# esp8285.net
KiCad netlist of a schematic drawn in EAGLE
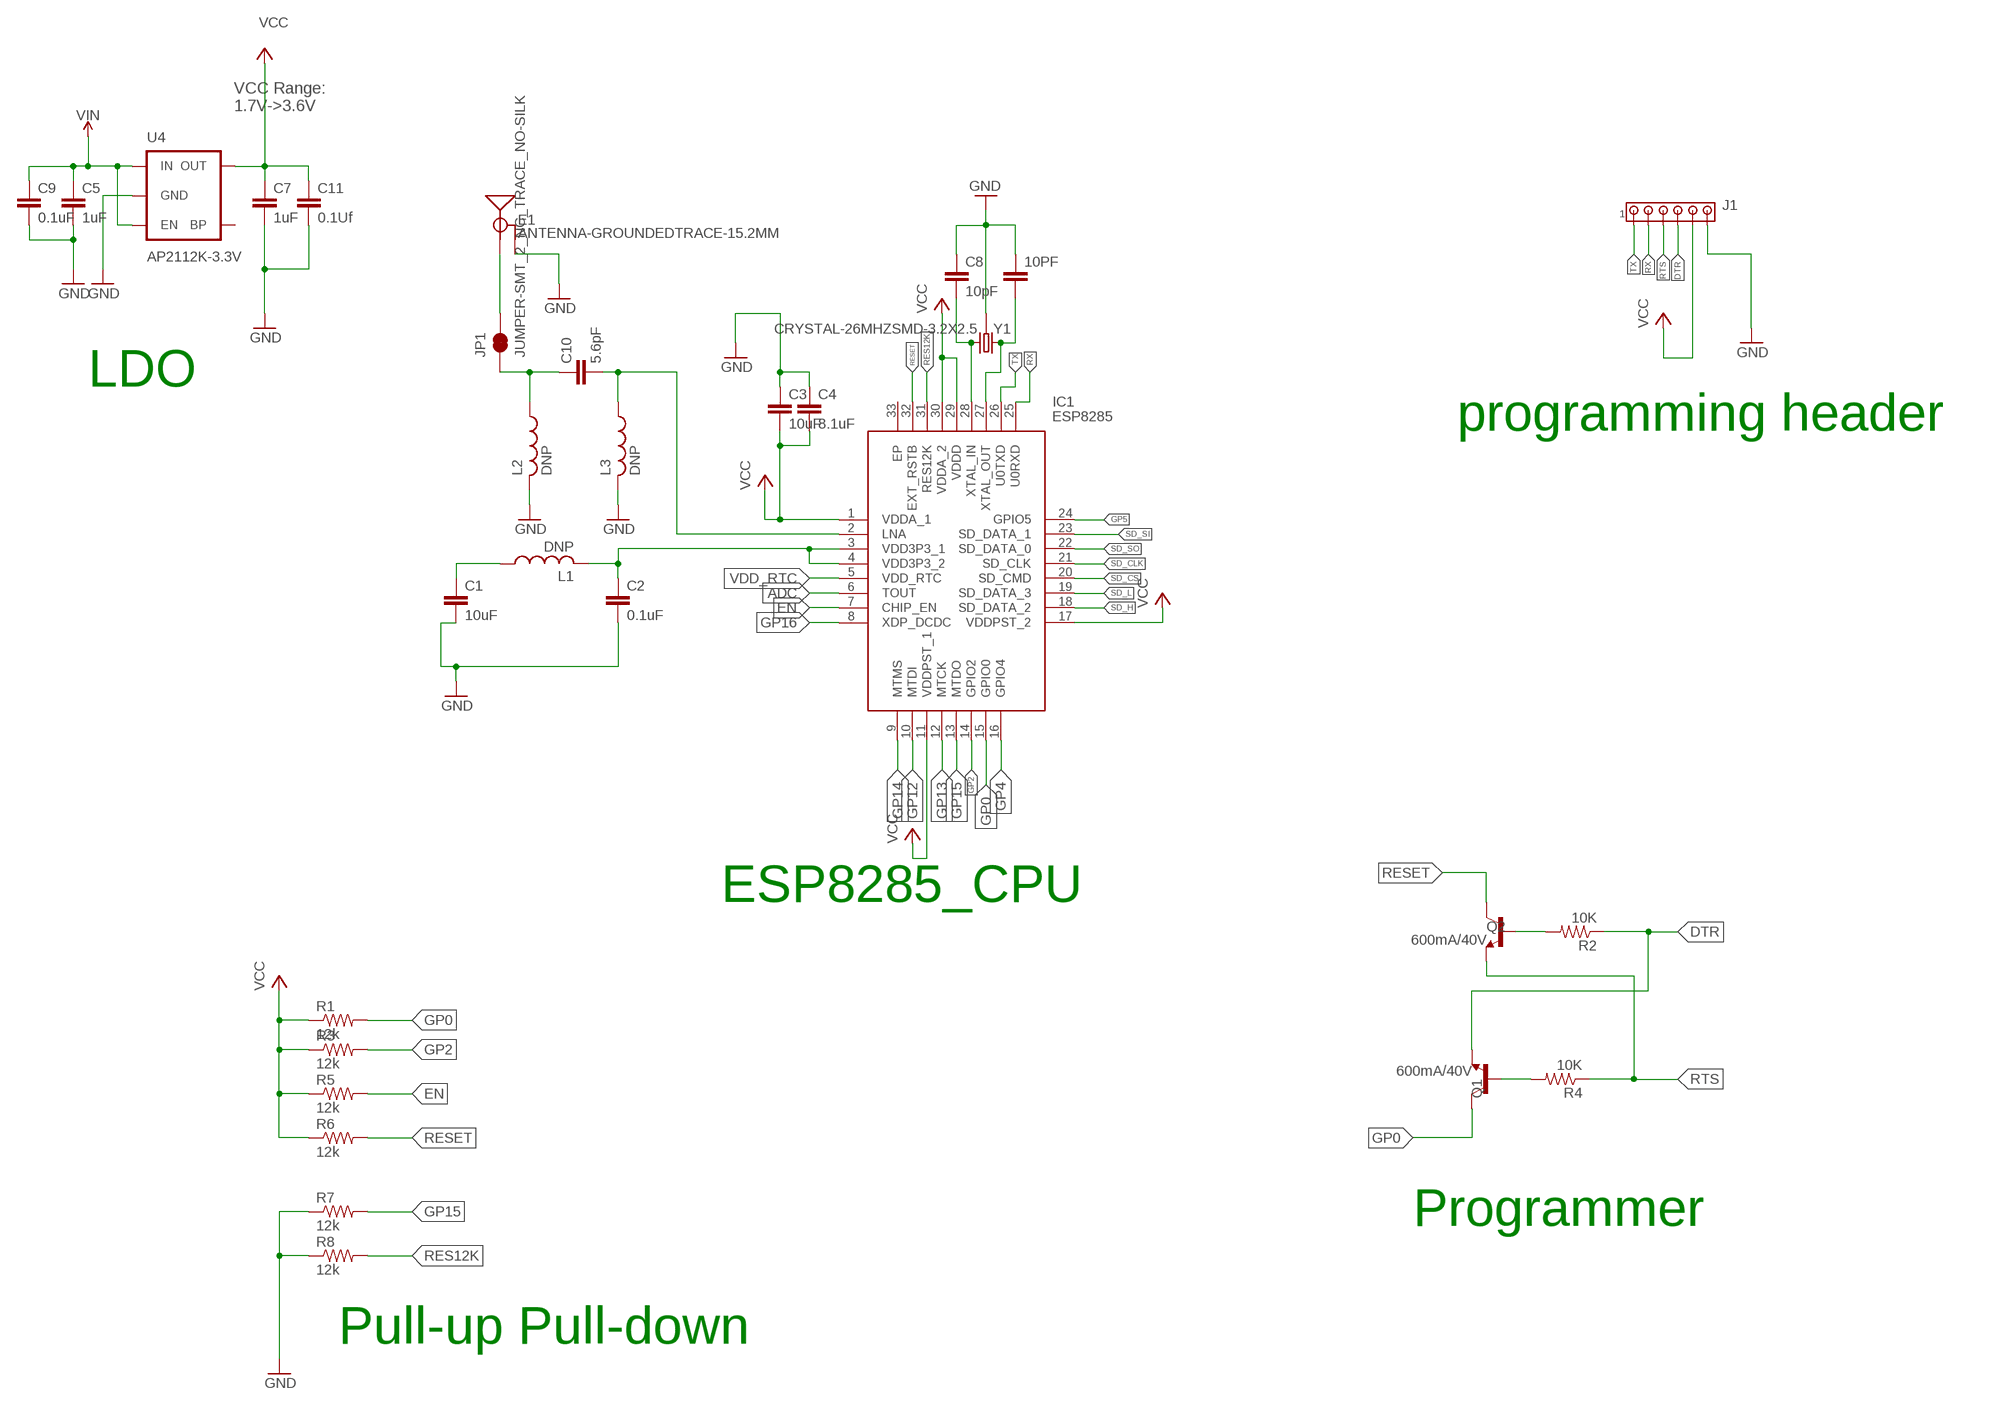
[diagram p0: schematic, sheet 1]

(export (version "E")
  (design (tool "Eeschema 10.0.6"))
  (components
    (comp (ref "10PF")
      (value "C-EUC0603")
      (footprint "eagle-import:C0603")
      (libsource (lib "eagle-import") (part "C-EUC0603"))
    )
    (comp (ref "C1")
      (value "10uF")
      (footprint "eagle-import:C0603")
      (libsource (lib "eagle-import") (part "C-EUC0603"))
    )
    (comp (ref "C2")
      (value "0.1uF")
      (footprint "eagle-import:C0603")
      (libsource (lib "eagle-import") (part "C-EUC0603"))
    )
    (comp (ref "C3")
      (value "10uF")
      (footprint "eagle-import:C0603")
      (libsource (lib "eagle-import") (part "C-EUC0603"))
    )
    (comp (ref "C4")
      (value "8.1uF")
      (footprint "eagle-import:C0603")
      (libsource (lib "eagle-import") (part "C-EUC0603"))
    )
    (comp (ref "C5")
      (value "1uF")
      (footprint "eagle-import:C0603")
      (libsource (lib "eagle-import") (part "C-EUC0603"))
    )
    (comp (ref "C7")
      (value "1uF")
      (footprint "eagle-import:C0603")
      (libsource (lib "eagle-import") (part "C-EUC0603"))
    )
    (comp (ref "C8")
      (value "10pF")
      (footprint "eagle-import:C0603")
      (libsource (lib "eagle-import") (part "C-EUC0603"))
    )
    (comp (ref "C9")
      (value "0.1uF")
      (footprint "eagle-import:C0603")
      (libsource (lib "eagle-import") (part "C-EUC0603"))
    )
    (comp (ref "C10")
      (value "5.6pF")
      (footprint "eagle-import:C0603")
      (libsource (lib "eagle-import") (part "C-EUC0603"))
    )
    (comp (ref "C11")
      (value "0.1Uf")
      (footprint "eagle-import:C0603")
      (libsource (lib "eagle-import") (part "C-EUC0603"))
    )
    (comp (ref "E1")
      (value "ANTENNA-GROUNDEDTRACE-15.2MM")
      (footprint "eagle-import:TRACE_ANTENNA_2.4GHZ_15.2MM")
      (libsource (lib "eagle-import") (part "ANTENNA-GROUNDEDTRACE-15.2MM"))
    )
    (comp (ref "IC1")
      (value "ESP8285")
      (footprint "eagle-import:QFN50P500X500X90-33N")
      (fields (field (name "MOUSER_PART_NUMBER") "356-ESP8285"))
      (libsource (lib "eagle-import") (part "ESP8285"))
    )
    (comp (ref "J1")
      (value "MTA06-100")
      (footprint "eagle-import:10X06MTA")
      (libsource (lib "eagle-import") (part "MTA06-100"))
    )
    (comp (ref "JP1")
      (value "JUMPER-SMT_2_NC_TRACE_NO-SILK")
      (footprint "eagle-import:SMT-JUMPER_2_NC_TRACE_NO-SILK")
      (libsource (lib "eagle-import") (part "JUMPER-SMT_2_NC_TRACE_NO-SILK"))
    )
    (comp (ref "L1")
      (value "DNP")
      (footprint "eagle-import:L0603")
      (libsource (lib "eagle-import") (part "L-USL0603"))
    )
    (comp (ref "L2")
      (value "DNP")
      (footprint "eagle-import:L0603")
      (libsource (lib "eagle-import") (part "L-USL0603"))
    )
    (comp (ref "L3")
      (value "DNP")
      (footprint "eagle-import:L0603")
      (libsource (lib "eagle-import") (part "L-USL0603"))
    )
    (comp (ref "Q1")
      (value "600mA/40V")
      (footprint "eagle-import:SOT23-3")
      (libsource (lib "eagle-import") (part "TRANS_NPN-MMBT2222AL"))
    )
    (comp (ref "Q2")
      (value "600mA/40V")
      (footprint "eagle-import:SOT23-3")
      (libsource (lib "eagle-import") (part "TRANS_NPN-MMBT2222AL"))
    )
    (comp (ref "R1")
      (value "12k")
      (footprint "eagle-import:R0805")
      (libsource (lib "eagle-import") (part "R-US_R0805"))
    )
    (comp (ref "R2")
      (value "10K")
      (footprint "eagle-import:R0805")
      (libsource (lib "eagle-import") (part "rcl_334_R-US_R0805"))
    )
    (comp (ref "R3")
      (value "12k")
      (footprint "eagle-import:R0805")
      (libsource (lib "eagle-import") (part "R-US_R0805"))
    )
    (comp (ref "R4")
      (value "10K")
      (footprint "eagle-import:R0805")
      (libsource (lib "eagle-import") (part "rcl_334_R-US_R0805"))
    )
    (comp (ref "R5")
      (value "12k")
      (footprint "eagle-import:R0805")
      (libsource (lib "eagle-import") (part "R-US_R0805"))
    )
    (comp (ref "R6")
      (value "12k")
      (footprint "eagle-import:R0805")
      (libsource (lib "eagle-import") (part "R-US_R0805"))
    )
    (comp (ref "R7")
      (value "12k")
      (footprint "eagle-import:R0805")
      (libsource (lib "eagle-import") (part "R-US_R0805"))
    )
    (comp (ref "R8")
      (value "12k")
      (footprint "eagle-import:R0805")
      (libsource (lib "eagle-import") (part "R-US_R0805"))
    )
    (comp (ref "U4")
      (value "AP2112K-3.3V")
      (footprint "eagle-import:SOT23-5")
      (libsource (lib "eagle-import") (part "V_REG_LDOSMD"))
    )
    (comp (ref "Y1")
      (value "CRYSTAL-26MHZSMD-3.2X2.5")
      (footprint "eagle-import:CRYSTAL-SMD-3.2X2.5MM")
      (libsource (lib "eagle-import") (part "CRYSTAL-26MHZSMD-3.2X2.5"))
    )
  )
  (nets
    (net (code "1") (name "ADC") (class "Default")
      (node (ref "IC1") (pin "6") (pinfunction "TOUT_6") (pintype "bidirectional"))
    )
    (net (code "2") (name "DTR") (class "Default")
      (node (ref "J1") (pin "4") (pinfunction "4_4") (pintype "passive"))
      (node (ref "Q1") (pin "2") (pinfunction "E_2") (pintype "passive"))
      (node (ref "R2") (pin "1") (pinfunction "1_1") (pintype "passive"))
    )
    (net (code "3") (name "EN") (class "Default")
      (node (ref "IC1") (pin "7") (pinfunction "CHIP_EN_7") (pintype "bidirectional"))
      (node (ref "R5") (pin "2") (pinfunction "2_2") (pintype "passive"))
    )
    (net (code "4") (name "GND") (class "Default")
      (node (ref "10PF") (pin "1") (pinfunction "1_1") (pintype "passive"))
      (node (ref "C1") (pin "2") (pinfunction "2_2") (pintype "passive"))
      (node (ref "C11") (pin "2") (pinfunction "2_2") (pintype "passive"))
      (node (ref "C2") (pin "2") (pinfunction "2_2") (pintype "passive"))
      (node (ref "C3") (pin "1") (pinfunction "1_1") (pintype "passive"))
      (node (ref "C4") (pin "1") (pinfunction "1_1") (pintype "passive"))
      (node (ref "C5") (pin "2") (pinfunction "2_2") (pintype "passive"))
      (node (ref "C7") (pin "2") (pinfunction "2_2") (pintype "passive"))
      (node (ref "C8") (pin "1") (pinfunction "1_1") (pintype "passive"))
      (node (ref "C9") (pin "2") (pinfunction "2_2") (pintype "passive"))
      (node (ref "E1") (pin "GND") (pinfunction "GND_GND") (pintype "bidirectional"))
      (node (ref "J1") (pin "6") (pinfunction "6_6") (pintype "passive"))
      (node (ref "L2") (pin "2") (pinfunction "2_2") (pintype "passive"))
      (node (ref "L3") (pin "2") (pinfunction "2_2") (pintype "passive"))
      (node (ref "R7") (pin "1") (pinfunction "1_1") (pintype "passive"))
      (node (ref "R8") (pin "1") (pinfunction "1_1") (pintype "passive"))
      (node (ref "U4") (pin "2") (pinfunction "GND_2") (pintype "input"))
      (node (ref "Y1") (pin "2") (pinfunction "3_2") (pintype "passive"))
      (node (ref "Y1") (pin "4") (pinfunction "3_4") (pintype "passive"))
    )
    (net (code "5") (name "GP0") (class "Default")
      (node (ref "IC1") (pin "15") (pinfunction "GPIO0_15") (pintype "bidirectional"))
      (node (ref "Q1") (pin "3") (pinfunction "C_3") (pintype "passive"))
      (node (ref "R1") (pin "2") (pinfunction "2_2") (pintype "passive"))
    )
    (net (code "6") (name "GP2") (class "Default")
      (node (ref "IC1") (pin "14") (pinfunction "GPIO2_14") (pintype "bidirectional"))
      (node (ref "R3") (pin "2") (pinfunction "2_2") (pintype "passive"))
    )
    (net (code "7") (name "GP4") (class "Default")
      (node (ref "IC1") (pin "16") (pinfunction "GPIO4_16") (pintype "bidirectional"))
    )
    (net (code "8") (name "GP5") (class "Default")
      (node (ref "IC1") (pin "24") (pinfunction "GPIO5_24") (pintype "bidirectional"))
    )
    (net (code "9") (name "GP12") (class "Default")
      (node (ref "IC1") (pin "10") (pinfunction "MTDI_10") (pintype "bidirectional"))
    )
    (net (code "10") (name "GP13") (class "Default")
      (node (ref "IC1") (pin "12") (pinfunction "MTCK_12") (pintype "bidirectional"))
    )
    (net (code "11") (name "GP14") (class "Default")
      (node (ref "IC1") (pin "9") (pinfunction "MTMS_9") (pintype "bidirectional"))
    )
    (net (code "12") (name "GP15") (class "Default")
      (node (ref "IC1") (pin "13") (pinfunction "MTDO_13") (pintype "bidirectional"))
      (node (ref "R7") (pin "2") (pinfunction "2_2") (pintype "passive"))
    )
    (net (code "13") (name "GP16") (class "Default")
      (node (ref "IC1") (pin "8") (pinfunction "XDP_DCDC_8") (pintype "bidirectional"))
    )
    (net (code "14") (name "Net-(C1-Pad1)") (class "Default")
      (node (ref "C1") (pin "1") (pinfunction "1_1") (pintype "passive"))
      (node (ref "L1") (pin "1") (pinfunction "1_1") (pintype "passive"))
    )
    (net (code "15") (name "Net-(C10-Pad1)") (class "Default")
      (node (ref "C10") (pin "1") (pinfunction "1_1") (pintype "passive"))
      (node (ref "JP1") (pin "1") (pinfunction "1_1") (pintype "passive"))
      (node (ref "L2") (pin "1") (pinfunction "1_1") (pintype "passive"))
    )
    (net (code "16") (name "Net-(E1-SIGNAL)") (class "Default")
      (node (ref "E1") (pin "ANT") (pinfunction "SIGNAL_ANT") (pintype "bidirectional"))
      (node (ref "JP1") (pin "2") (pinfunction "2_2") (pintype "passive"))
    )
    (net (code "17") (name "Net-(IC1-LNA)") (class "Default")
      (node (ref "C10") (pin "2") (pinfunction "2_2") (pintype "passive"))
      (node (ref "IC1") (pin "2") (pinfunction "LNA_2") (pintype "bidirectional"))
      (node (ref "L3") (pin "1") (pinfunction "1_1") (pintype "passive"))
    )
    (net (code "18") (name "Net-(IC1-VDD3P3_1)") (class "Default")
      (node (ref "C2") (pin "1") (pinfunction "1_1") (pintype "passive"))
      (node (ref "IC1") (pin "3") (pinfunction "VDD3P3_1_3") (pintype "bidirectional"))
      (node (ref "IC1") (pin "4") (pinfunction "VDD3P3_2_4") (pintype "bidirectional"))
      (node (ref "L1") (pin "2") (pinfunction "2_2") (pintype "passive"))
    )
    (net (code "19") (name "Net-(IC1-XTAL_IN)") (class "Default")
      (node (ref "C8") (pin "2") (pinfunction "2_2") (pintype "passive"))
      (node (ref "IC1") (pin "28") (pinfunction "XTAL_IN_28") (pintype "bidirectional"))
      (node (ref "Y1") (pin "3") (pinfunction "2_3") (pintype "passive"))
    )
    (net (code "20") (name "Net-(IC1-XTAL_OUT)") (class "Default")
      (node (ref "10PF") (pin "2") (pinfunction "2_2") (pintype "passive"))
      (node (ref "IC1") (pin "27") (pinfunction "XTAL_OUT_27") (pintype "bidirectional"))
      (node (ref "Y1") (pin "1") (pinfunction "1_1") (pintype "passive"))
    )
    (net (code "21") (name "Net-(Q1-B)") (class "Default")
      (node (ref "Q1") (pin "1") (pinfunction "B_1") (pintype "passive"))
      (node (ref "R4") (pin "2") (pinfunction "2_2") (pintype "passive"))
    )
    (net (code "22") (name "Net-(Q2-B)") (class "Default")
      (node (ref "Q2") (pin "1") (pinfunction "B_1") (pintype "passive"))
      (node (ref "R2") (pin "2") (pinfunction "2_2") (pintype "passive"))
    )
    (net (code "23") (name "RES12K") (class "Default")
      (node (ref "IC1") (pin "31") (pinfunction "RES12K_31") (pintype "bidirectional"))
      (node (ref "R8") (pin "2") (pinfunction "2_2") (pintype "passive"))
    )
    (net (code "24") (name "RESET") (class "Default")
      (node (ref "IC1") (pin "32") (pinfunction "EXT_RSTB_32") (pintype "bidirectional"))
      (node (ref "Q2") (pin "3") (pinfunction "C_3") (pintype "passive"))
      (node (ref "R6") (pin "2") (pinfunction "2_2") (pintype "passive"))
    )
    (net (code "25") (name "RTS") (class "Default")
      (node (ref "J1") (pin "3") (pinfunction "3_3") (pintype "passive"))
      (node (ref "Q2") (pin "2") (pinfunction "E_2") (pintype "passive"))
      (node (ref "R4") (pin "1") (pinfunction "1_1") (pintype "passive"))
    )
    (net (code "26") (name "RX") (class "Default")
      (node (ref "IC1") (pin "25") (pinfunction "U0RXD_25") (pintype "bidirectional"))
      (node (ref "J1") (pin "2") (pinfunction "2_2") (pintype "passive"))
    )
    (net (code "27") (name "SD_CLK") (class "Default")
      (node (ref "IC1") (pin "21") (pinfunction "SD_CLK_21") (pintype "bidirectional"))
    )
    (net (code "28") (name "SD_CS") (class "Default")
      (node (ref "IC1") (pin "20") (pinfunction "SD_CMD_20") (pintype "bidirectional"))
    )
    (net (code "29") (name "SD_H") (class "Default")
      (node (ref "IC1") (pin "18") (pinfunction "SD_DATA_2_18") (pintype "bidirectional"))
    )
    (net (code "30") (name "SD_L") (class "Default")
      (node (ref "IC1") (pin "19") (pinfunction "SD_DATA_3_19") (pintype "bidirectional"))
    )
    (net (code "31") (name "SD_SI") (class "Default")
      (node (ref "IC1") (pin "23") (pinfunction "SD_DATA_1_23") (pintype "bidirectional"))
    )
    (net (code "32") (name "SD_SO") (class "Default")
      (node (ref "IC1") (pin "22") (pinfunction "SD_DATA_0_22") (pintype "bidirectional"))
    )
    (net (code "33") (name "TX") (class "Default")
      (node (ref "IC1") (pin "26") (pinfunction "U0TXD_26") (pintype "bidirectional"))
      (node (ref "J1") (pin "1") (pinfunction "1_1") (pintype "passive"))
    )
    (net (code "34") (name "VCC") (class "Default")
      (node (ref "C11") (pin "1") (pinfunction "1_1") (pintype "passive"))
      (node (ref "C3") (pin "2") (pinfunction "2_2") (pintype "passive"))
      (node (ref "C4") (pin "2") (pinfunction "2_2") (pintype "passive"))
      (node (ref "C7") (pin "1") (pinfunction "1_1") (pintype "passive"))
      (node (ref "IC1") (pin "1") (pinfunction "VDDA_1_1") (pintype "bidirectional"))
      (node (ref "IC1") (pin "11") (pinfunction "VDDPST_1_11") (pintype "bidirectional"))
      (node (ref "IC1") (pin "17") (pinfunction "VDDPST_2_17") (pintype "bidirectional"))
      (node (ref "IC1") (pin "29") (pinfunction "VDDD_29") (pintype "bidirectional"))
      (node (ref "IC1") (pin "30") (pinfunction "VDDA_2_30") (pintype "bidirectional"))
      (node (ref "J1") (pin "5") (pinfunction "5_5") (pintype "passive"))
      (node (ref "R1") (pin "1") (pinfunction "1_1") (pintype "passive"))
      (node (ref "R3") (pin "1") (pinfunction "1_1") (pintype "passive"))
      (node (ref "R5") (pin "1") (pinfunction "1_1") (pintype "passive"))
      (node (ref "R6") (pin "1") (pinfunction "1_1") (pintype "passive"))
      (node (ref "U4") (pin "5") (pinfunction "OUT_5") (pintype "passive"))
    )
    (net (code "35") (name "VDD_RTC") (class "Default")
      (node (ref "IC1") (pin "5") (pinfunction "VDD_RTC_5") (pintype "bidirectional"))
    )
    (net (code "36") (name "VIN") (class "Default")
      (node (ref "C5") (pin "1") (pinfunction "1_1") (pintype "passive"))
      (node (ref "C9") (pin "1") (pinfunction "1_1") (pintype "passive"))
      (node (ref "U4") (pin "1") (pinfunction "IN_1") (pintype "input"))
      (node (ref "U4") (pin "3") (pinfunction "EN_3") (pintype "input"))
    )
    (net (code "37") (name "unconnected-(IC1-EP-Pad33)") (class "Default")
      (node (ref "IC1") (pin "33") (pinfunction "EP_33") (pintype "bidirectional"))
    )
    (net (code "38") (name "unconnected-(U4-BP-Pad4)") (class "Default")
      (node (ref "U4") (pin "4") (pinfunction "BP_4") (pintype "input"))
    )
  )
)
